# psupply2.net
KiCad netlist of a schematic drawn in EAGLE
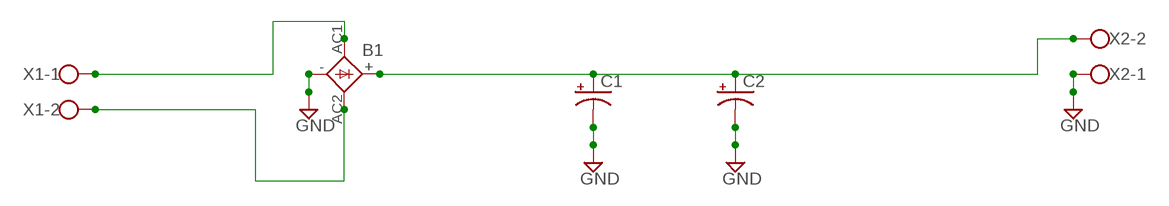
[diagram p0: schematic, sheet 1]

(export (version "E")
  (design (tool "Eeschema 10.0.6"))
  (components
    (comp (ref "B1")
      (value "GBPC80X")
      (footprint "eagle-import:GBPC80X")
      (libsource (lib "eagle-import") (part "GBPC80X"))
    )
    (comp (ref "C1")
      (value "CPOL-USE5-4")
      (footprint "eagle-import:E5-4")
      (libsource (lib "eagle-import") (part "CPOL-USE5-4"))
    )
    (comp (ref "C2")
      (value "CPOL-USE7.5-18")
      (footprint "eagle-import:E7,5-18")
      (libsource (lib "eagle-import") (part "CPOL-USE7.5-18"))
    )
    (comp (ref "X1")
      (value "W237-102")
      (footprint "eagle-import:W237-102")
      (fields (field (name "MPN") "237-102"))
      (libsource (lib "eagle-import") (part "W237-102"))
    )
    (comp (ref "X2")
      (value "W237-102")
      (footprint "eagle-import:W237-102")
      (fields (field (name "MPN") "237-102"))
      (libsource (lib "eagle-import") (part "W237-102"))
    )
  )
  (nets
    (net (code "1") (name "GND") (class "Default")
      (node (ref "B1") (pin "-") (pinfunction "-_-") (pintype "passive"))
      (node (ref "C1") (pin "-") (pinfunction "-_-") (pintype "passive"))
      (node (ref "C2") (pin "-") (pinfunction "-_-") (pintype "passive"))
      (node (ref "X2") (pin "1") (pinfunction "KL_1") (pintype "passive"))
    )
    (net (code "2") (name "Net-(X1A-KL)") (class "Default")
      (node (ref "B1") (pin "AC1") (pinfunction "AC1_AC1") (pintype "passive"))
      (node (ref "X1") (pin "1") (pinfunction "KL_1") (pintype "passive"))
    )
    (net (code "3") (name "Net-(X1B-KL)") (class "Default")
      (node (ref "B1") (pin "AC2") (pinfunction "AC2_AC2") (pintype "passive"))
      (node (ref "X1") (pin "2") (pinfunction "KL_2") (pintype "passive"))
    )
    (net (code "4") (name "Net-(X2B-KL)") (class "Default")
      (node (ref "B1") (pin "+") (pinfunction "+_+") (pintype "passive"))
      (node (ref "C1") (pin "+") (pinfunction "+_+") (pintype "passive"))
      (node (ref "C2") (pin "+") (pinfunction "+_+") (pintype "passive"))
      (node (ref "X2") (pin "2") (pinfunction "KL_2") (pintype "passive"))
    )
  )
)
